# ControladorPOE.net
KiCad netlist of a schematic drawn in Altium Designer
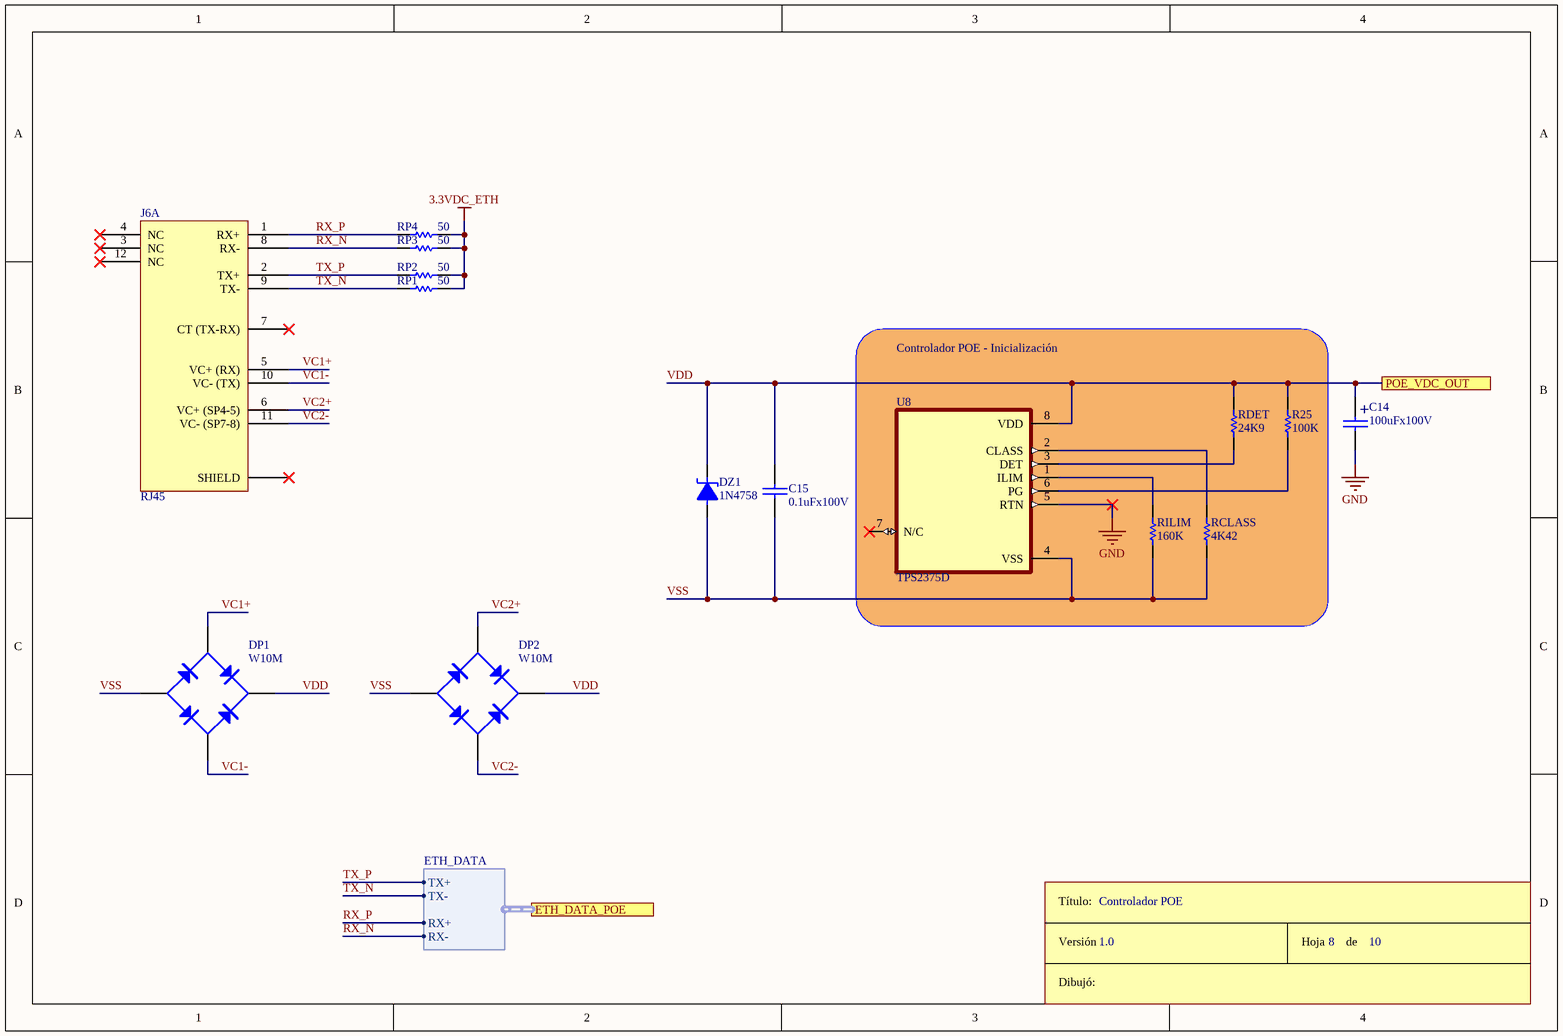
[diagram p0: ControladorPOE.SchDoc]

(export (version "E")
  (design (tool "Eeschema 10.0.6"))
  (components
    (comp (ref "C14") (value "100uFx100V") (footprint "CAP200RP") (libsource (lib "LIBEBAL") (part "CAPPOL")))
    (comp (ref "C15") (value "0.1uFx100V") (footprint "CAP300") (libsource (lib "LIBEBAL") (part "CAP")))
    (comp (ref "DP1")
      (value "W10M")
      (footprint "PUENTE - W10M")
      (description "Bridge Rectifier TH 1000V 1.5A")
      (libsource (lib "AditionalComponents") (part "W10M"))
    )
    (comp (ref "DP2")
      (value "W10M")
      (footprint "PUENTE - W10M")
      (description "Bridge Rectifier TH 1000V 1.5A")
      (libsource (lib "AditionalComponents") (part "W10M"))
    )
    (comp (ref "DZ1") (value "1N4758") (footprint "DO41") (libsource (lib "LIBEBAL") (part "DIODO ZENER")))
    (comp (ref "J6A")
      (value "RJ45")
      (footprint "ARJP11C-MB")
      (description "Magjack Connector for PoE")
      (libsource (lib "AditionalComponents") (part "ARJP11C-MBSC-L2"))
    )
    (comp (ref "R25") (value "100K") (footprint "RES300") (libsource (lib "LIBEBAL") (part "RES")))
    (comp (ref "RCLASS") (value "4K42") (footprint "RES300") (libsource (lib "LIBEBAL") (part "RES")))
    (comp (ref "RDET") (value "24K9") (footprint "RES300") (libsource (lib "LIBEBAL") (part "RES")))
    (comp (ref "RILIM") (value "160K") (footprint "RES300") (libsource (lib "LIBEBAL") (part "RES")))
    (comp (ref "ROT7") (value "Rótulo") (libsource (lib "LIB PIO IX") (part "Rótulo")))
    (comp (ref "RP1") (value "50") (footprint "1206") (libsource (lib "LIBEBAL") (part "RES")))
    (comp (ref "RP2") (value "50") (footprint "1206") (libsource (lib "LIBEBAL") (part "RES")))
    (comp (ref "RP3") (value "50") (footprint "1206") (libsource (lib "LIBEBAL") (part "RES")))
    (comp (ref "RP4") (value "50") (footprint "1206") (libsource (lib "LIBEBAL") (part "RES")))
    (comp (ref "U8")
      (value "TPS2375D")
      (footprint "SOIC127P599X175-8N")
      (description "Class 3 PoE PD with latch protection 8-SOIC -40 to 85")
      (fields (field (name "DIGI-KEY_PART_NUMBER") "296-26922-2-ND") (field (name "MF") "Texas Instruments"))
      (libsource (lib "TPS2375D_Rev2") (part "TPS2375D"))
    )
  )
  (nets
    (net (code "2") (name "/RX_N") (class "Default")
      (node (ref "J6A") (pin "8") (pinfunction "RX-_8") (pintype "passive"))
      (node (ref "RP3") (pin "1") (pinfunction "1_1") (pintype "passive"))
    )
    (net (code "3") (name "/RX_P") (class "Default")
      (node (ref "J6A") (pin "1") (pinfunction "RX+_1") (pintype "passive"))
      (node (ref "RP4") (pin "1") (pinfunction "1_1") (pintype "passive"))
    )
    (net (code "4") (name "/TX_N") (class "Default")
      (node (ref "J6A") (pin "9") (pinfunction "TX-_9") (pintype "passive"))
      (node (ref "RP1") (pin "1") (pinfunction "1_1") (pintype "passive"))
    )
    (net (code "5") (name "/TX_P") (class "Default")
      (node (ref "J6A") (pin "2") (pinfunction "TX+_2") (pintype "passive"))
      (node (ref "RP2") (pin "1") (pinfunction "1_1") (pintype "passive"))
    )
    (net (code "6") (name "/VC1+") (class "Default")
      (node (ref "DP1") (pin "2") (pinfunction "AC_2") (pintype "passive"))
      (node (ref "J6A") (pin "5") (pinfunction "VC+_(RX)_5") (pintype "passive"))
    )
    (net (code "7") (name "/VC1-") (class "Default")
      (node (ref "DP1") (pin "4") (pinfunction "AC_4") (pintype "passive"))
      (node (ref "J6A") (pin "10") (pinfunction "VC-_(TX)_10") (pintype "passive"))
    )
    (net (code "8") (name "/VC2+") (class "Default")
      (node (ref "DP2") (pin "2") (pinfunction "AC_2") (pintype "passive"))
      (node (ref "J6A") (pin "6") (pinfunction "VC+_(SP4-5)_6") (pintype "passive"))
    )
    (net (code "9") (name "/VC2-") (class "Default")
      (node (ref "DP2") (pin "4") (pinfunction "AC_4") (pintype "passive"))
      (node (ref "J6A") (pin "11") (pinfunction "VC-_(SP7-8)_11") (pintype "passive"))
    )
    (net (code "10") (name "/VDD") (class "Default")
      (node (ref "C14") (pin "1") (pinfunction "1_1") (pintype "passive"))
      (node (ref "C15") (pin "1") (pinfunction "1_1") (pintype "passive"))
      (node (ref "DP1") (pin "1") (pinfunction "V+_1") (pintype "passive"))
      (node (ref "DP2") (pin "1") (pinfunction "V+_1") (pintype "passive"))
      (node (ref "DZ1") (pin "2") (pinfunction "2_2") (pintype "passive"))
      (node (ref "R25") (pin "2") (pinfunction "2_2") (pintype "passive"))
      (node (ref "RDET") (pin "2") (pinfunction "2_2") (pintype "passive"))
      (node (ref "U8") (pin "8") (pinfunction "VDD_8") (pintype "power_in"))
    )
    (net (code "11") (name "/VSS") (class "Default")
      (node (ref "C15") (pin "2") (pinfunction "2_2") (pintype "passive"))
      (node (ref "DP1") (pin "3") (pinfunction "V-_3") (pintype "passive"))
      (node (ref "DP2") (pin "3") (pinfunction "V-_3") (pintype "passive"))
      (node (ref "DZ1") (pin "1") (pinfunction "1_1") (pintype "passive"))
      (node (ref "RCLASS") (pin "1") (pinfunction "1_1") (pintype "passive"))
      (node (ref "RILIM") (pin "1") (pinfunction "1_1") (pintype "passive"))
      (node (ref "U8") (pin "4") (pinfunction "VSS_4") (pintype "power_in"))
    )
    (net (code "13") (name "3.3VDC_ETH") (class "Default")
      (node (ref "RP1") (pin "2") (pinfunction "2_2") (pintype "passive"))
      (node (ref "RP2") (pin "2") (pinfunction "2_2") (pintype "passive"))
      (node (ref "RP3") (pin "2") (pinfunction "2_2") (pintype "passive"))
      (node (ref "RP4") (pin "2") (pinfunction "2_2") (pintype "passive"))
    )
    (net (code "14") (name "GND") (class "Default")
      (node (ref "C14") (pin "2") (pinfunction "2_2") (pintype "passive"))
      (node (ref "U8") (pin "5") (pinfunction "RTN_5") (pintype "output"))
    )
    (net (code "15") (name "Net-(U8-CLASS)") (class "Default")
      (node (ref "RCLASS") (pin "2") (pinfunction "2_2") (pintype "passive"))
      (node (ref "U8") (pin "2") (pinfunction "CLASS_2") (pintype "output"))
    )
    (net (code "16") (name "Net-(U8-DET)") (class "Default")
      (node (ref "RDET") (pin "1") (pinfunction "1_1") (pintype "passive"))
      (node (ref "U8") (pin "3") (pinfunction "DET_3") (pintype "output"))
    )
    (net (code "17") (name "Net-(U8-ILIM)") (class "Default")
      (node (ref "RILIM") (pin "2") (pinfunction "2_2") (pintype "passive"))
      (node (ref "U8") (pin "1") (pinfunction "ILIM_1") (pintype "output"))
    )
    (net (code "18") (name "Net-(U8-PG)") (class "Default")
      (node (ref "R25") (pin "1") (pinfunction "1_1") (pintype "passive"))
      (node (ref "U8") (pin "6") (pinfunction "PG_6") (pintype "output"))
    )
    (net (code "19") (name "unconnected-(J6A-CT_(TX-RX)-Pad7)") (class "Default")
      (node (ref "J6A") (pin "7") (pinfunction "CT_(TX-RX)_7") (pintype "passive+no_connect"))
    )
    (net (code "20") (name "unconnected-(J6A-NC-Pad3)") (class "Default")
      (node (ref "J6A") (pin "3") (pinfunction "NC_3") (pintype "passive+no_connect"))
    )
    (net (code "21") (name "unconnected-(J6A-NC-Pad4)") (class "Default")
      (node (ref "J6A") (pin "4") (pinfunction "NC_4") (pintype "passive+no_connect"))
    )
    (net (code "22") (name "unconnected-(J6A-NC-Pad12)") (class "Default")
      (node (ref "J6A") (pin "12") (pinfunction "NC_12") (pintype "passive+no_connect"))
    )
    (net (code "23") (name "unconnected-(J6A-PadSHIELD)") (class "Default")
      (node (ref "J6A") (pin "SHIELD") (pinfunction "SHIELD_SHIELD") (pintype "passive+no_connect"))
    )
    (net (code "24") (name "unconnected-(U8-N{slash}C-Pad7)") (class "Default")
      (node (ref "U8") (pin "7") (pinfunction "N/C_7") (pintype "bidirectional+no_connect"))
    )
  )
)
